# micro_game.net
KiCad netlist of a schematic drawn in EAGLE
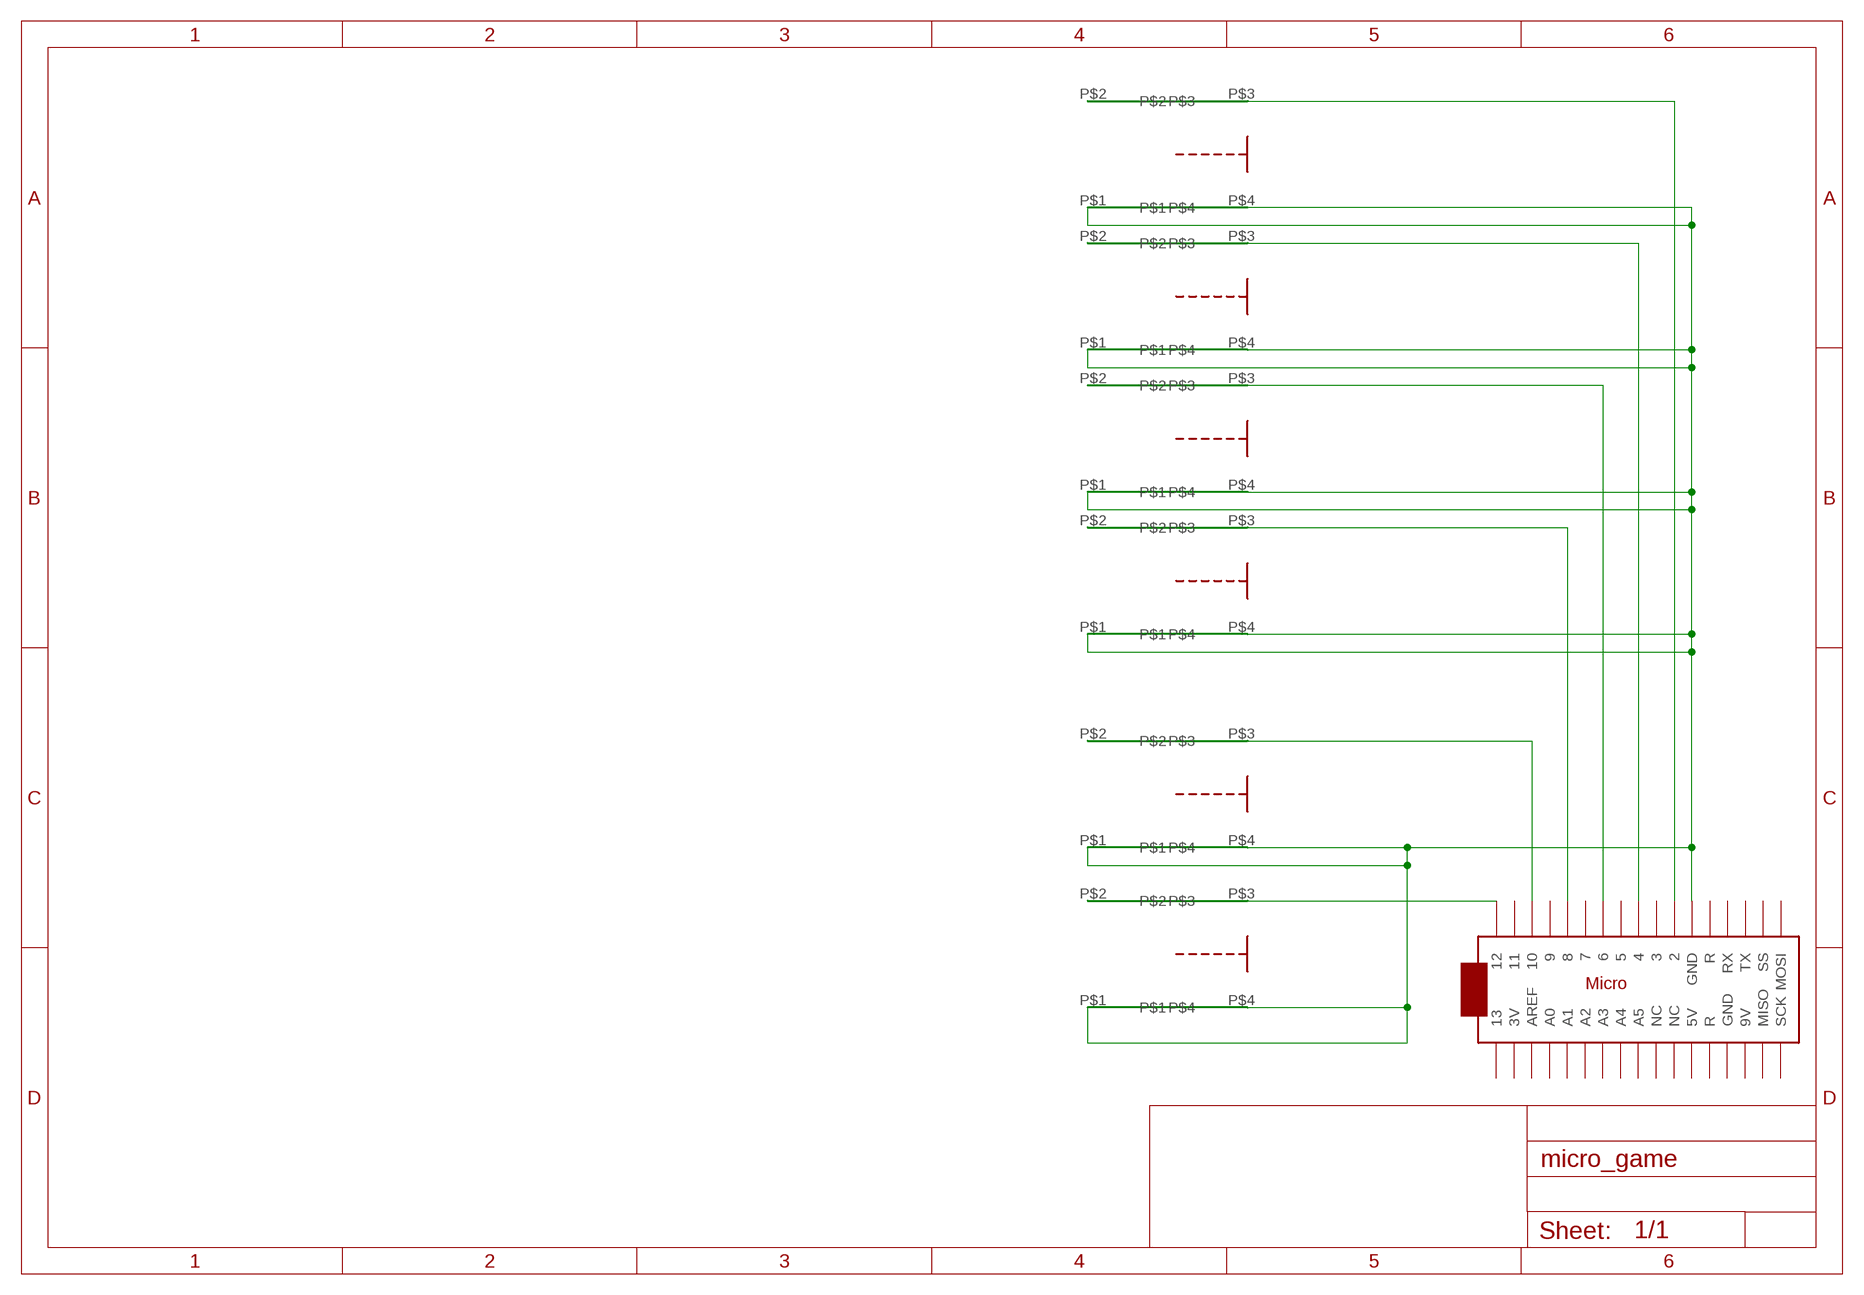
[diagram p0: schematic, sheet 1]

(export (version "E")
  (design (tool "Eeschema 10.0.6"))
  (components
    (comp (ref "U$1")
      (value "ARDUINOMICRO")
      (footprint "eagle-import:ARDUINOMICRO")
      (libsource (lib "eagle-import") (part "ARDUINOMICRO"))
    )
    (comp (ref "U$2")
      (value "MICRO_GAME_SWITCH")
      (footprint "eagle-import:MICRO_GAME_SWITCH")
      (libsource (lib "eagle-import") (part "MICRO_GAME_SWITCH"))
    )
    (comp (ref "U$3")
      (value "MICRO_GAME_SWITCH")
      (footprint "eagle-import:MICRO_GAME_SWITCH")
      (libsource (lib "eagle-import") (part "MICRO_GAME_SWITCH"))
    )
    (comp (ref "U$4")
      (value "MICRO_GAME_SWITCH")
      (footprint "eagle-import:MICRO_GAME_SWITCH")
      (libsource (lib "eagle-import") (part "MICRO_GAME_SWITCH"))
    )
    (comp (ref "U$5")
      (value "MICRO_GAME_SWITCH")
      (footprint "eagle-import:MICRO_GAME_SWITCH")
      (libsource (lib "eagle-import") (part "MICRO_GAME_SWITCH"))
    )
    (comp (ref "U$6")
      (value "MICRO_GAME_SWITCH")
      (footprint "eagle-import:MICRO_GAME_SWITCH")
      (libsource (lib "eagle-import") (part "MICRO_GAME_SWITCH"))
    )
    (comp (ref "U$7")
      (value "MICRO_GAME_SWITCH")
      (footprint "eagle-import:MICRO_GAME_SWITCH")
      (libsource (lib "eagle-import") (part "MICRO_GAME_SWITCH"))
    )
  )
  (nets
    (net (code "1") (name "Net-(U$1-2)") (class "Default")
      (node (ref "U$1") (pin "P$11") (pinfunction "2_P$11") (pintype "bidirectional"))
      (node (ref "U$4") (pin "P$3") (pinfunction "P$3_P$3") (pintype "bidirectional"))
    )
    (net (code "2") (name "Net-(U$1-4)") (class "Default")
      (node (ref "U$1") (pin "P$9") (pinfunction "4_P$9") (pintype "bidirectional"))
      (node (ref "U$2") (pin "P$3") (pinfunction "P$3_P$3") (pintype "bidirectional"))
    )
    (net (code "3") (name "Net-(U$1-6)") (class "Default")
      (node (ref "U$1") (pin "P$7") (pinfunction "6_P$7") (pintype "bidirectional"))
      (node (ref "U$3") (pin "P$3") (pinfunction "P$3_P$3") (pintype "bidirectional"))
    )
    (net (code "4") (name "Net-(U$1-8)") (class "Default")
      (node (ref "U$1") (pin "P$5") (pinfunction "8_P$5") (pintype "bidirectional"))
      (node (ref "U$5") (pin "P$3") (pinfunction "P$3_P$3") (pintype "bidirectional"))
    )
    (net (code "5") (name "Net-(U$1-10)") (class "Default")
      (node (ref "U$1") (pin "P$3") (pinfunction "10_P$3") (pintype "bidirectional"))
      (node (ref "U$6") (pin "P$3") (pinfunction "P$3_P$3") (pintype "bidirectional"))
    )
    (net (code "6") (name "Net-(U$1-12)") (class "Default")
      (node (ref "U$1") (pin "P$1") (pinfunction "12_P$1") (pintype "bidirectional"))
      (node (ref "U$7") (pin "P$3") (pinfunction "P$3_P$3") (pintype "bidirectional"))
    )
    (net (code "7") (name "Net-(U$1-GND-PadP$21)") (class "Default")
      (node (ref "U$1") (pin "P$21") (pinfunction "GND_P$21") (pintype "bidirectional"))
      (node (ref "U$2") (pin "P$1") (pinfunction "P$1_P$1") (pintype "bidirectional"))
      (node (ref "U$2") (pin "P$4") (pinfunction "P$4_P$4") (pintype "bidirectional"))
      (node (ref "U$3") (pin "P$1") (pinfunction "P$1_P$1") (pintype "bidirectional"))
      (node (ref "U$3") (pin "P$4") (pinfunction "P$4_P$4") (pintype "bidirectional"))
      (node (ref "U$4") (pin "P$1") (pinfunction "P$1_P$1") (pintype "bidirectional"))
      (node (ref "U$4") (pin "P$4") (pinfunction "P$4_P$4") (pintype "bidirectional"))
      (node (ref "U$5") (pin "P$1") (pinfunction "P$1_P$1") (pintype "bidirectional"))
      (node (ref "U$5") (pin "P$4") (pinfunction "P$4_P$4") (pintype "bidirectional"))
      (node (ref "U$6") (pin "P$1") (pinfunction "P$1_P$1") (pintype "bidirectional"))
      (node (ref "U$6") (pin "P$4") (pinfunction "P$4_P$4") (pintype "bidirectional"))
      (node (ref "U$7") (pin "P$1") (pinfunction "P$1_P$1") (pintype "bidirectional"))
      (node (ref "U$7") (pin "P$4") (pinfunction "P$4_P$4") (pintype "bidirectional"))
    )
    (net (code "8") (name "unconnected-(U$1-3-PadP$10)") (class "Default")
      (node (ref "U$1") (pin "P$10") (pinfunction "3_P$10") (pintype "bidirectional"))
    )
    (net (code "9") (name "unconnected-(U$1-3V-PadP$33)") (class "Default")
      (node (ref "U$1") (pin "P$33") (pinfunction "3V_P$33") (pintype "bidirectional"))
    )
    (net (code "10") (name "unconnected-(U$1-5-PadP$8)") (class "Default")
      (node (ref "U$1") (pin "P$8") (pinfunction "5_P$8") (pintype "bidirectional"))
    )
    (net (code "11") (name "unconnected-(U$1-5V-PadP$23)") (class "Default")
      (node (ref "U$1") (pin "P$23") (pinfunction "5V_P$23") (pintype "bidirectional"))
    )
    (net (code "12") (name "unconnected-(U$1-7-PadP$6)") (class "Default")
      (node (ref "U$1") (pin "P$6") (pinfunction "7_P$6") (pintype "bidirectional"))
    )
    (net (code "13") (name "unconnected-(U$1-9-PadP$4)") (class "Default")
      (node (ref "U$1") (pin "P$4") (pinfunction "9_P$4") (pintype "bidirectional"))
    )
    (net (code "14") (name "unconnected-(U$1-9V-PadP$20)") (class "Default")
      (node (ref "U$1") (pin "P$20") (pinfunction "9V_P$20") (pintype "bidirectional"))
    )
    (net (code "15") (name "unconnected-(U$1-11-PadP$2)") (class "Default")
      (node (ref "U$1") (pin "P$2") (pinfunction "11_P$2") (pintype "bidirectional"))
    )
    (net (code "16") (name "unconnected-(U$1-13-PadP$34)") (class "Default")
      (node (ref "U$1") (pin "P$34") (pinfunction "13_P$34") (pintype "bidirectional"))
    )
    (net (code "17") (name "unconnected-(U$1-A0-PadP$31)") (class "Default")
      (node (ref "U$1") (pin "P$31") (pinfunction "A0_P$31") (pintype "bidirectional"))
    )
    (net (code "18") (name "unconnected-(U$1-A1-PadP$30)") (class "Default")
      (node (ref "U$1") (pin "P$30") (pinfunction "A1_P$30") (pintype "bidirectional"))
    )
    (net (code "19") (name "unconnected-(U$1-A2-PadP$29)") (class "Default")
      (node (ref "U$1") (pin "P$29") (pinfunction "A2_P$29") (pintype "bidirectional"))
    )
    (net (code "20") (name "unconnected-(U$1-A3-PadP$28)") (class "Default")
      (node (ref "U$1") (pin "P$28") (pinfunction "A3_P$28") (pintype "bidirectional"))
    )
    (net (code "21") (name "unconnected-(U$1-A4-PadP$27)") (class "Default")
      (node (ref "U$1") (pin "P$27") (pinfunction "A4_P$27") (pintype "bidirectional"))
    )
    (net (code "22") (name "unconnected-(U$1-A5-PadP$26)") (class "Default")
      (node (ref "U$1") (pin "P$26") (pinfunction "A5_P$26") (pintype "bidirectional"))
    )
    (net (code "23") (name "unconnected-(U$1-AREF-PadP$32)") (class "Default")
      (node (ref "U$1") (pin "P$32") (pinfunction "AREF_P$32") (pintype "bidirectional"))
    )
    (net (code "24") (name "unconnected-(U$1-GND-PadP$12)") (class "Default")
      (node (ref "U$1") (pin "P$12") (pinfunction "GND_P$12") (pintype "bidirectional"))
    )
    (net (code "25") (name "unconnected-(U$1-MISO-PadP$19)") (class "Default")
      (node (ref "U$1") (pin "P$19") (pinfunction "MISO_P$19") (pintype "bidirectional"))
    )
    (net (code "26") (name "unconnected-(U$1-MOSI-PadP$17)") (class "Default")
      (node (ref "U$1") (pin "P$17") (pinfunction "MOSI_P$17") (pintype "bidirectional"))
    )
    (net (code "27") (name "unconnected-(U$1-NC-PadP$24)") (class "Default")
      (node (ref "U$1") (pin "P$24") (pinfunction "NC_P$24") (pintype "bidirectional"))
    )
    (net (code "28") (name "unconnected-(U$1-NC-PadP$25)") (class "Default")
      (node (ref "U$1") (pin "P$25") (pinfunction "NC_P$25") (pintype "bidirectional"))
    )
    (net (code "29") (name "unconnected-(U$1-R-PadP$13)") (class "Default")
      (node (ref "U$1") (pin "P$13") (pinfunction "R_P$13") (pintype "bidirectional"))
    )
    (net (code "30") (name "unconnected-(U$1-R-PadP$22)") (class "Default")
      (node (ref "U$1") (pin "P$22") (pinfunction "R_P$22") (pintype "bidirectional"))
    )
    (net (code "31") (name "unconnected-(U$1-RX-PadP$14)") (class "Default")
      (node (ref "U$1") (pin "P$14") (pinfunction "RX_P$14") (pintype "bidirectional"))
    )
    (net (code "32") (name "unconnected-(U$1-SCK-PadP$18)") (class "Default")
      (node (ref "U$1") (pin "P$18") (pinfunction "SCK_P$18") (pintype "bidirectional"))
    )
    (net (code "33") (name "unconnected-(U$1-SS-PadP$16)") (class "Default")
      (node (ref "U$1") (pin "P$16") (pinfunction "SS_P$16") (pintype "bidirectional"))
    )
    (net (code "34") (name "unconnected-(U$1-TX-PadP$15)") (class "Default")
      (node (ref "U$1") (pin "P$15") (pinfunction "TX_P$15") (pintype "bidirectional"))
    )
    (net (code "35") (name "unconnected-(U$2-PadP$2)") (class "Default")
      (node (ref "U$2") (pin "P$2") (pinfunction "P$2_P$2") (pintype "bidirectional"))
    )
    (net (code "36") (name "unconnected-(U$3-PadP$2)") (class "Default")
      (node (ref "U$3") (pin "P$2") (pinfunction "P$2_P$2") (pintype "bidirectional"))
    )
    (net (code "37") (name "unconnected-(U$4-PadP$2)") (class "Default")
      (node (ref "U$4") (pin "P$2") (pinfunction "P$2_P$2") (pintype "bidirectional"))
    )
    (net (code "38") (name "unconnected-(U$5-PadP$2)") (class "Default")
      (node (ref "U$5") (pin "P$2") (pinfunction "P$2_P$2") (pintype "bidirectional"))
    )
    (net (code "39") (name "unconnected-(U$6-PadP$2)") (class "Default")
      (node (ref "U$6") (pin "P$2") (pinfunction "P$2_P$2") (pintype "bidirectional"))
    )
    (net (code "40") (name "unconnected-(U$7-PadP$2)") (class "Default")
      (node (ref "U$7") (pin "P$2") (pinfunction "P$2_P$2") (pintype "bidirectional"))
    )
  )
)
